# Pong_Schematic_v5.net
KiCad netlist of a schematic drawn in EAGLE
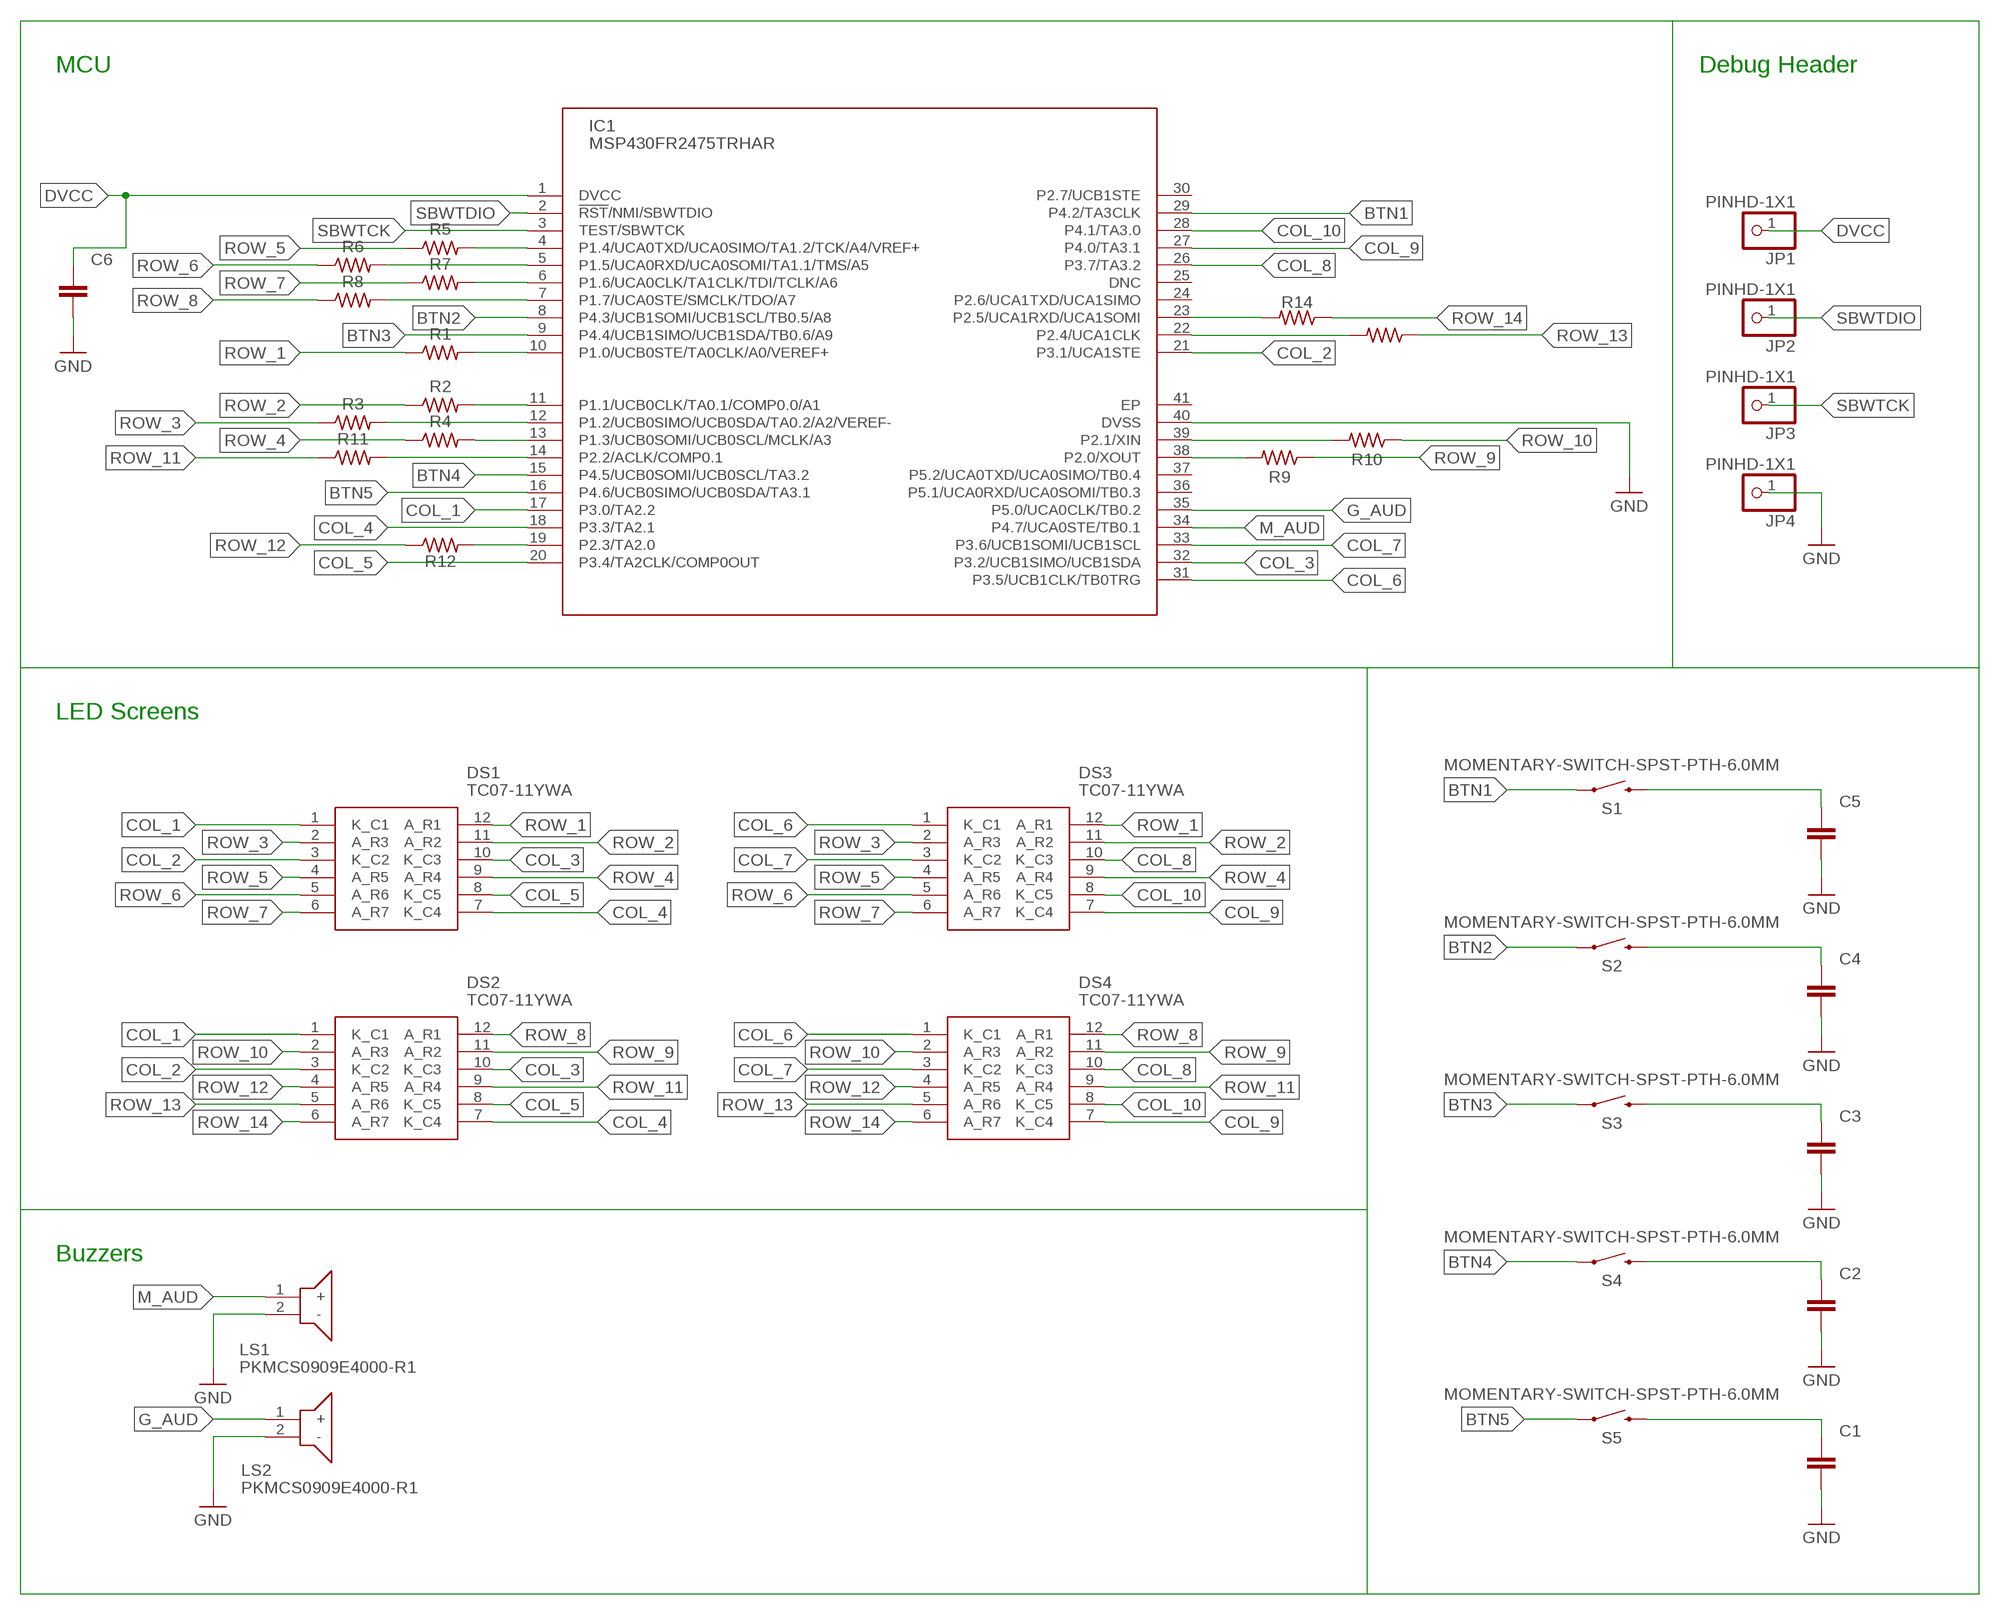
[diagram p0: schematic, sheet 1]

(export (version "E")
  (design (tool "Eeschema 10.0.6"))
  (components
    (comp (ref "C1")
      (value "C_CHIP-0805(2012-METRIC)")
      (footprint "eagle-import:CAPC2012X110")
      (libsource (lib "eagle-import") (part "CCHIP-0805(2012-METRIC)_"))
    )
    (comp (ref "C2")
      (value "C_CHIP-0805(2012-METRIC)")
      (footprint "eagle-import:CAPC2012X110")
      (libsource (lib "eagle-import") (part "CCHIP-0805(2012-METRIC)_"))
    )
    (comp (ref "C3")
      (value "C_CHIP-0805(2012-METRIC)")
      (footprint "eagle-import:CAPC2012X110")
      (libsource (lib "eagle-import") (part "CCHIP-0805(2012-METRIC)_"))
    )
    (comp (ref "C4")
      (value "C_CHIP-0805(2012-METRIC)")
      (footprint "eagle-import:CAPC2012X110")
      (libsource (lib "eagle-import") (part "CCHIP-0805(2012-METRIC)_"))
    )
    (comp (ref "C5")
      (value "C_CHIP-0805(2012-METRIC)")
      (footprint "eagle-import:CAPC2012X110")
      (libsource (lib "eagle-import") (part "CCHIP-0805(2012-METRIC)_"))
    )
    (comp (ref "C6")
      (value "C_CHIP-0805(2012-METRIC)")
      (footprint "eagle-import:CAPC2012X110")
      (libsource (lib "eagle-import") (part "CCHIP-0805(2012-METRIC)_"))
    )
    (comp (ref "DS1")
      (value "TC07-11YWA")
      (footprint "eagle-import:TC0711YWA")
      (fields (field (name "MOUSER_PART_NUMBER") "604-TC07-11YWA"))
      (libsource (lib "eagle-import") (part "TC07-11YWA"))
    )
    (comp (ref "DS2")
      (value "TC07-11YWA")
      (footprint "eagle-import:TC0711YWA")
      (fields (field (name "MOUSER_PART_NUMBER") "604-TC07-11YWA"))
      (libsource (lib "eagle-import") (part "TC07-11YWA"))
    )
    (comp (ref "DS3")
      (value "TC07-11YWA")
      (footprint "eagle-import:TC0711YWA")
      (fields (field (name "MOUSER_PART_NUMBER") "604-TC07-11YWA"))
      (libsource (lib "eagle-import") (part "TC07-11YWA"))
    )
    (comp (ref "DS4")
      (value "TC07-11YWA")
      (footprint "eagle-import:TC0711YWA")
      (fields (field (name "MOUSER_PART_NUMBER") "604-TC07-11YWA"))
      (libsource (lib "eagle-import") (part "TC07-11YWA"))
    )
    (comp (ref "IC1")
      (value "MSP430FR2475TRHAR")
      (footprint "eagle-import:QFN50P600X600X100-41N")
      (fields (field (name "MOUSER_PART_NUMBER") "595-SP430FR2475TRHAR"))
      (libsource (lib "eagle-import") (part "MSP430FR2475TRHAR"))
    )
    (comp (ref "JP1")
      (value "PINHD-1X1")
      (footprint "eagle-import:1X01")
      (libsource (lib "eagle-import") (part "PINHD-1X1"))
    )
    (comp (ref "JP2")
      (value "PINHD-1X1")
      (footprint "eagle-import:1X01")
      (libsource (lib "eagle-import") (part "PINHD-1X1"))
    )
    (comp (ref "JP3")
      (value "PINHD-1X1")
      (footprint "eagle-import:1X01")
      (libsource (lib "eagle-import") (part "PINHD-1X1"))
    )
    (comp (ref "JP4")
      (value "PINHD-1X1")
      (footprint "eagle-import:1X01")
      (libsource (lib "eagle-import") (part "PINHD-1X1"))
    )
    (comp (ref "LS1")
      (value "PKMCS0909E4000-R1")
      (footprint "eagle-import:PKMCS0909E4000R1")
      (fields (field (name "MOUSER_PART_NUMBER") "81-PKMCS0909E4000-R1"))
      (libsource (lib "eagle-import") (part "PKMCS0909E4000-R1"))
    )
    (comp (ref "LS2")
      (value "PKMCS0909E4000-R1")
      (footprint "eagle-import:PKMCS0909E4000R1")
      (fields (field (name "MOUSER_PART_NUMBER") "81-PKMCS0909E4000-R1"))
      (libsource (lib "eagle-import") (part "PKMCS0909E4000-R1"))
    )
    (comp (ref "R1")
      (value "R-US_CHIP-0805(2012-METRIC)")
      (footprint "eagle-import:RESC2012X65")
      (libsource (lib "eagle-import") (part "R-USCHIP-0805(2012-METRIC)_"))
    )
    (comp (ref "R2")
      (value "R-US_CHIP-0805(2012-METRIC)")
      (footprint "eagle-import:RESC2012X65")
      (libsource (lib "eagle-import") (part "R-USCHIP-0805(2012-METRIC)_"))
    )
    (comp (ref "R3")
      (value "R-US_CHIP-0805(2012-METRIC)")
      (footprint "eagle-import:RESC2012X65")
      (libsource (lib "eagle-import") (part "R-USCHIP-0805(2012-METRIC)_"))
    )
    (comp (ref "R4")
      (value "R-US_CHIP-0805(2012-METRIC)")
      (footprint "eagle-import:RESC2012X65")
      (libsource (lib "eagle-import") (part "R-USCHIP-0805(2012-METRIC)_"))
    )
    (comp (ref "R5")
      (value "R-US_CHIP-0805(2012-METRIC)")
      (footprint "eagle-import:RESC2012X65")
      (libsource (lib "eagle-import") (part "R-USCHIP-0805(2012-METRIC)_"))
    )
    (comp (ref "R6")
      (value "R-US_CHIP-0805(2012-METRIC)")
      (footprint "eagle-import:RESC2012X65")
      (libsource (lib "eagle-import") (part "R-USCHIP-0805(2012-METRIC)_"))
    )
    (comp (ref "R7")
      (value "R-US_CHIP-0805(2012-METRIC)")
      (footprint "eagle-import:RESC2012X65")
      (libsource (lib "eagle-import") (part "R-USCHIP-0805(2012-METRIC)_"))
    )
    (comp (ref "R8")
      (value "R-US_CHIP-0805(2012-METRIC)")
      (footprint "eagle-import:RESC2012X65")
      (libsource (lib "eagle-import") (part "R-USCHIP-0805(2012-METRIC)_"))
    )
    (comp (ref "R9")
      (value "R-US_CHIP-0805(2012-METRIC)")
      (footprint "eagle-import:RESC2012X65")
      (libsource (lib "eagle-import") (part "R-USCHIP-0805(2012-METRIC)_"))
    )
    (comp (ref "R10")
      (value "R-US_CHIP-0805(2012-METRIC)")
      (footprint "eagle-import:RESC2012X65")
      (libsource (lib "eagle-import") (part "R-USCHIP-0805(2012-METRIC)_"))
    )
    (comp (ref "R11")
      (value "R-US_CHIP-0805(2012-METRIC)")
      (footprint "eagle-import:RESC2012X65")
      (libsource (lib "eagle-import") (part "R-USCHIP-0805(2012-METRIC)_"))
    )
    (comp (ref "R12")
      (value "R-US_CHIP-0805(2012-METRIC)")
      (footprint "eagle-import:RESC2012X65")
      (libsource (lib "eagle-import") (part "R-USCHIP-0805(2012-METRIC)_"))
    )
    (comp (ref "R13")
      (value "R-US_CHIP-0805(2012-METRIC)")
      (footprint "eagle-import:RESC2012X65")
      (libsource (lib "eagle-import") (part "R-USCHIP-0805(2012-METRIC)_"))
    )
    (comp (ref "R14")
      (value "R-US_CHIP-0805(2012-METRIC)")
      (footprint "eagle-import:RESC2012X65")
      (libsource (lib "eagle-import") (part "R-USCHIP-0805(2012-METRIC)_"))
    )
    (comp (ref "S1")
      (value "MOMENTARY-SWITCH-SPST-PTH-6.0MM")
      (footprint "eagle-import:TACTILE_SWITCH_PTH_6.0MM")
      (libsource (lib "eagle-import") (part "MOMENTARY-SWITCH-SPST-PTH-6.0MM"))
    )
    (comp (ref "S2")
      (value "MOMENTARY-SWITCH-SPST-PTH-6.0MM")
      (footprint "eagle-import:TACTILE_SWITCH_PTH_6.0MM")
      (libsource (lib "eagle-import") (part "MOMENTARY-SWITCH-SPST-PTH-6.0MM"))
    )
    (comp (ref "S3")
      (value "MOMENTARY-SWITCH-SPST-PTH-6.0MM")
      (footprint "eagle-import:TACTILE_SWITCH_PTH_6.0MM")
      (libsource (lib "eagle-import") (part "MOMENTARY-SWITCH-SPST-PTH-6.0MM"))
    )
    (comp (ref "S4")
      (value "MOMENTARY-SWITCH-SPST-PTH-6.0MM")
      (footprint "eagle-import:TACTILE_SWITCH_PTH_6.0MM")
      (libsource (lib "eagle-import") (part "MOMENTARY-SWITCH-SPST-PTH-6.0MM"))
    )
    (comp (ref "S5")
      (value "MOMENTARY-SWITCH-SPST-PTH-6.0MM")
      (footprint "eagle-import:TACTILE_SWITCH_PTH_6.0MM")
      (libsource (lib "eagle-import") (part "MOMENTARY-SWITCH-SPST-PTH-6.0MM"))
    )
  )
  (nets
    (net (code "1") (name "BTN1") (class "Default")
      (node (ref "IC1") (pin "29") (pinfunction "P4.2/TA3CLK_29") (pintype "bidirectional"))
      (node (ref "S1") (pin "1") (pinfunction "1_1") (pintype "passive"))
    )
    (net (code "2") (name "BTN2") (class "Default")
      (node (ref "IC1") (pin "8") (pinfunction "P4.3/UCB1SOMI/UCB1SCL/TB0.5/A8_8") (pintype "bidirectional"))
      (node (ref "S2") (pin "1") (pinfunction "1_1") (pintype "passive"))
    )
    (net (code "3") (name "BTN3") (class "Default")
      (node (ref "IC1") (pin "9") (pinfunction "P4.4/UCB1SIMO/UCB1SDA/TB0.6/A9_9") (pintype "bidirectional"))
      (node (ref "S3") (pin "1") (pinfunction "1_1") (pintype "passive"))
    )
    (net (code "4") (name "BTN4") (class "Default")
      (node (ref "IC1") (pin "15") (pinfunction "P4.5/UCB0SOMI/UCB0SCL/TA3.2_15") (pintype "bidirectional"))
      (node (ref "S4") (pin "1") (pinfunction "1_1") (pintype "passive"))
    )
    (net (code "5") (name "BTN5") (class "Default")
      (node (ref "IC1") (pin "16") (pinfunction "P4.6/UCB0SIMO/UCB0SDA/TA3.1_16") (pintype "bidirectional"))
      (node (ref "S5") (pin "1") (pinfunction "1_1") (pintype "passive"))
    )
    (net (code "6") (name "COL_1") (class "Default")
      (node (ref "DS1") (pin "1") (pinfunction "K_C1_1") (pintype "bidirectional"))
      (node (ref "DS2") (pin "1") (pinfunction "K_C1_1") (pintype "bidirectional"))
      (node (ref "IC1") (pin "17") (pinfunction "P3.0/TA2.2_17") (pintype "bidirectional"))
    )
    (net (code "7") (name "COL_2") (class "Default")
      (node (ref "DS1") (pin "3") (pinfunction "K_C2_3") (pintype "bidirectional"))
      (node (ref "DS2") (pin "3") (pinfunction "K_C2_3") (pintype "bidirectional"))
      (node (ref "IC1") (pin "21") (pinfunction "P3.1/UCA1STE_21") (pintype "bidirectional"))
    )
    (net (code "8") (name "COL_3") (class "Default")
      (node (ref "DS1") (pin "10") (pinfunction "K_C3_10") (pintype "bidirectional"))
      (node (ref "DS2") (pin "10") (pinfunction "K_C3_10") (pintype "bidirectional"))
      (node (ref "IC1") (pin "32") (pinfunction "P3.2/UCB1SIMO/UCB1SDA_32") (pintype "bidirectional"))
    )
    (net (code "9") (name "COL_4") (class "Default")
      (node (ref "DS1") (pin "7") (pinfunction "K_C4_7") (pintype "bidirectional"))
      (node (ref "DS2") (pin "7") (pinfunction "K_C4_7") (pintype "bidirectional"))
      (node (ref "IC1") (pin "18") (pinfunction "P3.3/TA2.1_18") (pintype "bidirectional"))
    )
    (net (code "10") (name "COL_5") (class "Default")
      (node (ref "DS1") (pin "8") (pinfunction "K_C5_8") (pintype "bidirectional"))
      (node (ref "DS2") (pin "8") (pinfunction "K_C5_8") (pintype "bidirectional"))
      (node (ref "IC1") (pin "20") (pinfunction "P3.4/TA2CLK/COMP0OUT_20") (pintype "bidirectional"))
    )
    (net (code "11") (name "COL_6") (class "Default")
      (node (ref "DS3") (pin "1") (pinfunction "K_C1_1") (pintype "bidirectional"))
      (node (ref "DS4") (pin "1") (pinfunction "K_C1_1") (pintype "bidirectional"))
      (node (ref "IC1") (pin "31") (pinfunction "P3.5/UCB1CLK/TB0TRG_31") (pintype "bidirectional"))
    )
    (net (code "12") (name "COL_7") (class "Default")
      (node (ref "DS3") (pin "3") (pinfunction "K_C2_3") (pintype "bidirectional"))
      (node (ref "DS4") (pin "3") (pinfunction "K_C2_3") (pintype "bidirectional"))
      (node (ref "IC1") (pin "33") (pinfunction "P3.6/UCB1SOMI/UCB1SCL_33") (pintype "bidirectional"))
    )
    (net (code "13") (name "COL_8") (class "Default")
      (node (ref "DS3") (pin "10") (pinfunction "K_C3_10") (pintype "bidirectional"))
      (node (ref "DS4") (pin "10") (pinfunction "K_C3_10") (pintype "bidirectional"))
      (node (ref "IC1") (pin "26") (pinfunction "P3.7/TA3.2_26") (pintype "bidirectional"))
    )
    (net (code "14") (name "COL_9") (class "Default")
      (node (ref "DS3") (pin "7") (pinfunction "K_C4_7") (pintype "bidirectional"))
      (node (ref "DS4") (pin "7") (pinfunction "K_C4_7") (pintype "bidirectional"))
      (node (ref "IC1") (pin "27") (pinfunction "P4.0/TA3.1_27") (pintype "bidirectional"))
    )
    (net (code "15") (name "COL_10") (class "Default")
      (node (ref "DS3") (pin "8") (pinfunction "K_C5_8") (pintype "bidirectional"))
      (node (ref "DS4") (pin "8") (pinfunction "K_C5_8") (pintype "bidirectional"))
      (node (ref "IC1") (pin "28") (pinfunction "P4.1/TA3.0_28") (pintype "bidirectional"))
    )
    (net (code "16") (name "DVCC") (class "Default")
      (node (ref "C6") (pin "1") (pinfunction "1_1") (pintype "passive"))
      (node (ref "IC1") (pin "1") (pinfunction "DVCC_1") (pintype "bidirectional"))
      (node (ref "JP1") (pin "1") (pinfunction "1_1") (pintype "passive"))
    )
    (net (code "17") (name "GND") (class "Default")
      (node (ref "C1") (pin "2") (pinfunction "2_2") (pintype "passive"))
      (node (ref "C2") (pin "2") (pinfunction "2_2") (pintype "passive"))
      (node (ref "C3") (pin "2") (pinfunction "2_2") (pintype "passive"))
      (node (ref "C4") (pin "2") (pinfunction "2_2") (pintype "passive"))
      (node (ref "C5") (pin "2") (pinfunction "2_2") (pintype "passive"))
      (node (ref "C6") (pin "2") (pinfunction "2_2") (pintype "passive"))
      (node (ref "IC1") (pin "40") (pinfunction "DVSS_40") (pintype "bidirectional"))
      (node (ref "JP4") (pin "1") (pinfunction "1_1") (pintype "passive"))
      (node (ref "LS1") (pin "2") (pinfunction "-_2") (pintype "bidirectional"))
      (node (ref "LS2") (pin "2") (pinfunction "-_2") (pintype "bidirectional"))
    )
    (net (code "18") (name "G_AUD") (class "Default")
      (node (ref "IC1") (pin "35") (pinfunction "P5.0/UCA0CLK/TB0.2_35") (pintype "bidirectional"))
      (node (ref "LS2") (pin "1") (pinfunction "+_1") (pintype "bidirectional"))
    )
    (net (code "19") (name "M_AUD") (class "Default")
      (node (ref "IC1") (pin "34") (pinfunction "P4.7/UCA0STE/TB0.1_34") (pintype "bidirectional"))
      (node (ref "LS1") (pin "1") (pinfunction "+_1") (pintype "bidirectional"))
    )
    (net (code "20") (name "Net-(IC1-P1.0{slash}UCB0STE{slash}TA0CLK{slash}A0{slash}VEREF+)") (class "Default")
      (node (ref "IC1") (pin "10") (pinfunction "P1.0/UCB0STE/TA0CLK/A0/VEREF+_10") (pintype "bidirectional"))
      (node (ref "R1") (pin "2") (pinfunction "2_2") (pintype "passive"))
    )
    (net (code "21") (name "Net-(IC1-P1.1{slash}UCB0CLK{slash}TA0.1{slash}COMP0.0{slash}A1)") (class "Default")
      (node (ref "IC1") (pin "11") (pinfunction "P1.1/UCB0CLK/TA0.1/COMP0.0/A1_11") (pintype "bidirectional"))
      (node (ref "R2") (pin "2") (pinfunction "2_2") (pintype "passive"))
    )
    (net (code "22") (name "Net-(IC1-P1.2{slash}UCB0SIMO{slash}UCB0SDA{slash}TA0.2{slash}A2{slash}VEREF-)") (class "Default")
      (node (ref "IC1") (pin "12") (pinfunction "P1.2/UCB0SIMO/UCB0SDA/TA0.2/A2/VEREF-_12") (pintype "bidirectional"))
      (node (ref "R3") (pin "2") (pinfunction "2_2") (pintype "passive"))
    )
    (net (code "23") (name "Net-(IC1-P1.3{slash}UCB0SOMI{slash}UCB0SCL{slash}MCLK{slash}A3)") (class "Default")
      (node (ref "IC1") (pin "13") (pinfunction "P1.3/UCB0SOMI/UCB0SCL/MCLK/A3_13") (pintype "bidirectional"))
      (node (ref "R4") (pin "2") (pinfunction "2_2") (pintype "passive"))
    )
    (net (code "24") (name "Net-(IC1-P1.4{slash}UCA0TXD{slash}UCA0SIMO{slash}TA1.2{slash}TCK{slash}A4{slash}VREF+)") (class "Default")
      (node (ref "IC1") (pin "4") (pinfunction "P1.4/UCA0TXD/UCA0SIMO/TA1.2/TCK/A4/VREF+_4") (pintype "bidirectional"))
      (node (ref "R5") (pin "2") (pinfunction "2_2") (pintype "passive"))
    )
    (net (code "25") (name "Net-(IC1-P1.5{slash}UCA0RXD{slash}UCA0SOMI{slash}TA1.1{slash}TMS{slash}A5)") (class "Default")
      (node (ref "IC1") (pin "5") (pinfunction "P1.5/UCA0RXD/UCA0SOMI/TA1.1/TMS/A5_5") (pintype "bidirectional"))
      (node (ref "R6") (pin "2") (pinfunction "2_2") (pintype "passive"))
    )
    (net (code "26") (name "Net-(IC1-P1.6{slash}UCA0CLK{slash}TA1CLK{slash}TDI{slash}TCLK{slash}A6)") (class "Default")
      (node (ref "IC1") (pin "6") (pinfunction "P1.6/UCA0CLK/TA1CLK/TDI/TCLK/A6_6") (pintype "bidirectional"))
      (node (ref "R7") (pin "2") (pinfunction "2_2") (pintype "passive"))
    )
    (net (code "27") (name "Net-(IC1-P1.7{slash}UCA0STE{slash}SMCLK{slash}TDO{slash}A7)") (class "Default")
      (node (ref "IC1") (pin "7") (pinfunction "P1.7/UCA0STE/SMCLK/TDO/A7_7") (pintype "bidirectional"))
      (node (ref "R8") (pin "2") (pinfunction "2_2") (pintype "passive"))
    )
    (net (code "28") (name "Net-(IC1-P2.0{slash}XOUT)") (class "Default")
      (node (ref "IC1") (pin "38") (pinfunction "P2.0/XOUT_38") (pintype "bidirectional"))
      (node (ref "R9") (pin "2") (pinfunction "2_2") (pintype "passive"))
    )
    (net (code "29") (name "Net-(IC1-P2.1{slash}XIN)") (class "Default")
      (node (ref "IC1") (pin "39") (pinfunction "P2.1/XIN_39") (pintype "bidirectional"))
      (node (ref "R10") (pin "2") (pinfunction "2_2") (pintype "passive"))
    )
    (net (code "30") (name "Net-(IC1-P2.2{slash}ACLK{slash}COMP0.1)") (class "Default")
      (node (ref "IC1") (pin "14") (pinfunction "P2.2/ACLK/COMP0.1_14") (pintype "bidirectional"))
      (node (ref "R11") (pin "2") (pinfunction "2_2") (pintype "passive"))
    )
    (net (code "31") (name "Net-(IC1-P2.3{slash}TA2.0)") (class "Default")
      (node (ref "IC1") (pin "19") (pinfunction "P2.3/TA2.0_19") (pintype "bidirectional"))
      (node (ref "R12") (pin "2") (pinfunction "2_2") (pintype "passive"))
    )
    (net (code "32") (name "Net-(IC1-P2.4{slash}UCA1CLK)") (class "Default")
      (node (ref "IC1") (pin "22") (pinfunction "P2.4/UCA1CLK_22") (pintype "bidirectional"))
      (node (ref "R13") (pin "2") (pinfunction "2_2") (pintype "passive"))
    )
    (net (code "33") (name "Net-(IC1-P2.5{slash}UCA1RXD{slash}UCA1SOMI)") (class "Default")
      (node (ref "IC1") (pin "23") (pinfunction "P2.5/UCA1RXD/UCA1SOMI_23") (pintype "bidirectional"))
      (node (ref "R14") (pin "2") (pinfunction "2_2") (pintype "passive"))
    )
    (net (code "34") (name "Net-(S1-2)") (class "Default")
      (node (ref "C5") (pin "1") (pinfunction "1_1") (pintype "passive"))
      (node (ref "S1") (pin "3") (pinfunction "2_3") (pintype "passive"))
    )
    (net (code "35") (name "Net-(S2-2)") (class "Default")
      (node (ref "C4") (pin "1") (pinfunction "1_1") (pintype "passive"))
      (node (ref "S2") (pin "3") (pinfunction "2_3") (pintype "passive"))
    )
    (net (code "36") (name "Net-(S3-2)") (class "Default")
      (node (ref "C3") (pin "1") (pinfunction "1_1") (pintype "passive"))
      (node (ref "S3") (pin "3") (pinfunction "2_3") (pintype "passive"))
    )
    (net (code "37") (name "Net-(S4-2)") (class "Default")
      (node (ref "C2") (pin "1") (pinfunction "1_1") (pintype "passive"))
      (node (ref "S4") (pin "3") (pinfunction "2_3") (pintype "passive"))
    )
    (net (code "38") (name "Net-(S5-2)") (class "Default")
      (node (ref "C1") (pin "1") (pinfunction "1_1") (pintype "passive"))
      (node (ref "S5") (pin "3") (pinfunction "2_3") (pintype "passive"))
    )
    (net (code "39") (name "ROW_1") (class "Default")
      (node (ref "DS1") (pin "12") (pinfunction "A_R1_12") (pintype "bidirectional"))
      (node (ref "DS3") (pin "12") (pinfunction "A_R1_12") (pintype "bidirectional"))
      (node (ref "R1") (pin "1") (pinfunction "1_1") (pintype "passive"))
    )
    (net (code "40") (name "ROW_2") (class "Default")
      (node (ref "DS1") (pin "11") (pinfunction "A_R2_11") (pintype "bidirectional"))
      (node (ref "DS3") (pin "11") (pinfunction "A_R2_11") (pintype "bidirectional"))
      (node (ref "R2") (pin "1") (pinfunction "1_1") (pintype "passive"))
    )
    (net (code "41") (name "ROW_3") (class "Default")
      (node (ref "DS1") (pin "2") (pinfunction "A_R3_2") (pintype "bidirectional"))
      (node (ref "DS3") (pin "2") (pinfunction "A_R3_2") (pintype "bidirectional"))
      (node (ref "R3") (pin "1") (pinfunction "1_1") (pintype "passive"))
    )
    (net (code "42") (name "ROW_4") (class "Default")
      (node (ref "DS1") (pin "9") (pinfunction "A_R4_9") (pintype "bidirectional"))
      (node (ref "DS3") (pin "9") (pinfunction "A_R4_9") (pintype "bidirectional"))
      (node (ref "R4") (pin "1") (pinfunction "1_1") (pintype "passive"))
    )
    (net (code "43") (name "ROW_5") (class "Default")
      (node (ref "DS1") (pin "4") (pinfunction "A_R5_4") (pintype "bidirectional"))
      (node (ref "DS3") (pin "4") (pinfunction "A_R5_4") (pintype "bidirectional"))
      (node (ref "R5") (pin "1") (pinfunction "1_1") (pintype "passive"))
    )
    (net (code "44") (name "ROW_6") (class "Default")
      (node (ref "DS1") (pin "5") (pinfunction "A_R6_5") (pintype "bidirectional"))
      (node (ref "DS3") (pin "5") (pinfunction "A_R6_5") (pintype "bidirectional"))
      (node (ref "R6") (pin "1") (pinfunction "1_1") (pintype "passive"))
    )
    (net (code "45") (name "ROW_7") (class "Default")
      (node (ref "DS1") (pin "6") (pinfunction "A_R7_6") (pintype "bidirectional"))
      (node (ref "DS3") (pin "6") (pinfunction "A_R7_6") (pintype "bidirectional"))
      (node (ref "R7") (pin "1") (pinfunction "1_1") (pintype "passive"))
    )
    (net (code "46") (name "ROW_8") (class "Default")
      (node (ref "DS2") (pin "12") (pinfunction "A_R1_12") (pintype "bidirectional"))
      (node (ref "DS4") (pin "12") (pinfunction "A_R1_12") (pintype "bidirectional"))
      (node (ref "R8") (pin "1") (pinfunction "1_1") (pintype "passive"))
    )
    (net (code "47") (name "ROW_9") (class "Default")
      (node (ref "DS2") (pin "11") (pinfunction "A_R2_11") (pintype "bidirectional"))
      (node (ref "DS4") (pin "11") (pinfunction "A_R2_11") (pintype "bidirectional"))
      (node (ref "R9") (pin "1") (pinfunction "1_1") (pintype "passive"))
    )
    (net (code "48") (name "ROW_10") (class "Default")
      (node (ref "DS2") (pin "2") (pinfunction "A_R3_2") (pintype "bidirectional"))
      (node (ref "DS4") (pin "2") (pinfunction "A_R3_2") (pintype "bidirectional"))
      (node (ref "R10") (pin "1") (pinfunction "1_1") (pintype "passive"))
    )
    (net (code "49") (name "ROW_11") (class "Default")
      (node (ref "DS2") (pin "9") (pinfunction "A_R4_9") (pintype "bidirectional"))
      (node (ref "DS4") (pin "9") (pinfunction "A_R4_9") (pintype "bidirectional"))
      (node (ref "R11") (pin "1") (pinfunction "1_1") (pintype "passive"))
    )
    (net (code "50") (name "ROW_12") (class "Default")
      (node (ref "DS2") (pin "4") (pinfunction "A_R5_4") (pintype "bidirectional"))
      (node (ref "DS4") (pin "4") (pinfunction "A_R5_4") (pintype "bidirectional"))
      (node (ref "R12") (pin "1") (pinfunction "1_1") (pintype "passive"))
    )
    (net (code "51") (name "ROW_13") (class "Default")
      (node (ref "DS2") (pin "5") (pinfunction "A_R6_5") (pintype "bidirectional"))
      (node (ref "DS4") (pin "5") (pinfunction "A_R6_5") (pintype "bidirectional"))
      (node (ref "R13") (pin "1") (pinfunction "1_1") (pintype "passive"))
    )
    (net (code "52") (name "ROW_14") (class "Default")
      (node (ref "DS2") (pin "6") (pinfunction "A_R7_6") (pintype "bidirectional"))
      (node (ref "DS4") (pin "6") (pinfunction "A_R7_6") (pintype "bidirectional"))
      (node (ref "R14") (pin "1") (pinfunction "1_1") (pintype "passive"))
    )
    (net (code "53") (name "SBWTCK") (class "Default")
      (node (ref "IC1") (pin "3") (pinfunction "TEST/SBWTCK_3") (pintype "bidirectional"))
      (node (ref "JP3") (pin "1") (pinfunction "1_1") (pintype "passive"))
    )
    (net (code "54") (name "SBWTDIO") (class "Default")
      (node (ref "IC1") (pin "2") (pinfunction "~{RST}/NMI/SBWTDIO_2") (pintype "bidirectional"))
      (node (ref "JP2") (pin "1") (pinfunction "1_1") (pintype "passive"))
    )
    (net (code "55") (name "unconnected-(IC1-DNC-Pad25)") (class "Default")
      (node (ref "IC1") (pin "25") (pinfunction "DNC_25") (pintype "bidirectional"))
    )
    (net (code "56") (name "unconnected-(IC1-EP-Pad41)") (class "Default")
      (node (ref "IC1") (pin "41") (pinfunction "EP_41") (pintype "bidirectional"))
    )
    (net (code "57") (name "unconnected-(IC1-P2.6{slash}UCA1TXD{slash}UCA1SIMO-Pad24)") (class "Default")
      (node (ref "IC1") (pin "24") (pinfunction "P2.6/UCA1TXD/UCA1SIMO_24") (pintype "bidirectional"))
    )
    (net (code "58") (name "unconnected-(IC1-P2.7{slash}UCB1STE-Pad30)") (class "Default")
      (node (ref "IC1") (pin "30") (pinfunction "P2.7/UCB1STE_30") (pintype "bidirectional"))
    )
    (net (code "59") (name "unconnected-(IC1-P5.1{slash}UCA0RXD{slash}UCA0SOMI{slash}TB0.3-Pad36)") (class "Default")
      (node (ref "IC1") (pin "36") (pinfunction "P5.1/UCA0RXD/UCA0SOMI/TB0.3_36") (pintype "bidirectional"))
    )
    (net (code "60") (name "unconnected-(IC1-P5.2{slash}UCA0TXD{slash}UCA0SIMO{slash}TB0.4-Pad37)") (class "Default")
      (node (ref "IC1") (pin "37") (pinfunction "P5.2/UCA0TXD/UCA0SIMO/TB0.4_37") (pintype "bidirectional"))
    )
  )
)
